# MCU.net
KiCad netlist of a schematic drawn in Altium Designer
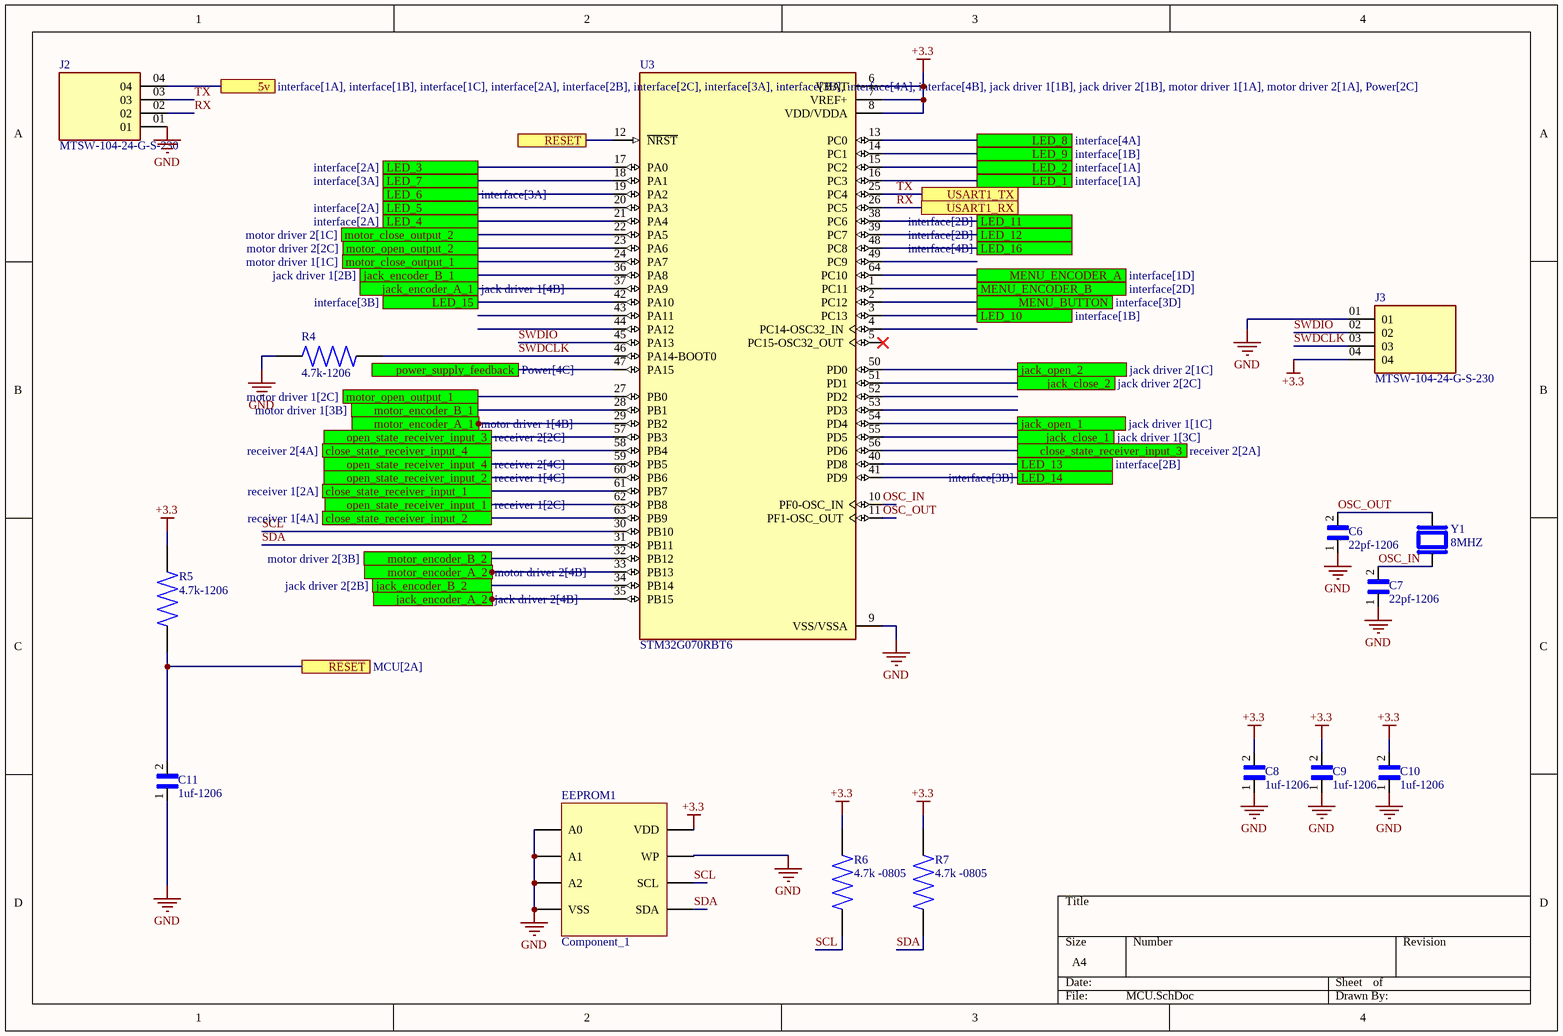
[diagram p0: MCU.SchDoc]

(export (version "E")
  (design (tool "Eeschema 10.0.6"))
  (components
    (comp (ref "C6")
      (value "22pf-1206")
      (footprint "CAPC3216X180N")
      (description "1ÂµF Â±20% 50V Ceramic Capacitor X8R 1206 (3216 Metric)")
      (fields (field (name "MF") "TDK") (field (name "MP") "CGA5L3X8R1H105M160AB"))
      (libsource (lib "cap-1206") (part "CGA5L3X8R1H105M160AB"))
    )
    (comp (ref "C7")
      (value "22pf-1206")
      (footprint "CAPC3216X180N")
      (description "1ÂµF Â±20% 50V Ceramic Capacitor X8R 1206 (3216 Metric)")
      (fields (field (name "MF") "TDK") (field (name "MP") "CGA5L3X8R1H105M160AB"))
      (libsource (lib "cap-1206") (part "CGA5L3X8R1H105M160AB"))
    )
    (comp (ref "C8")
      (value "1uf-1206")
      (footprint "CAPC3216X180N")
      (description "1ÂµF Â±20% 50V Ceramic Capacitor X8R 1206 (3216 Metric)")
      (fields (field (name "MF") "TDK") (field (name "MP") "CGA5L3X8R1H105M160AB"))
      (libsource (lib "cap-1206") (part "CGA5L3X8R1H105M160AB"))
    )
    (comp (ref "C9")
      (value "1uf-1206")
      (footprint "CAPC3216X180N")
      (description "1ÂµF Â±20% 50V Ceramic Capacitor X8R 1206 (3216 Metric)")
      (fields (field (name "MF") "TDK") (field (name "MP") "CGA5L3X8R1H105M160AB"))
      (libsource (lib "cap-1206") (part "CGA5L3X8R1H105M160AB"))
    )
    (comp (ref "C10")
      (value "1uf-1206")
      (footprint "CAPC3216X180N")
      (description "1ÂµF Â±20% 50V Ceramic Capacitor X8R 1206 (3216 Metric)")
      (fields (field (name "MF") "TDK") (field (name "MP") "CGA5L3X8R1H105M160AB"))
      (libsource (lib "cap-1206") (part "CGA5L3X8R1H105M160AB"))
    )
    (comp (ref "C11")
      (value "1uf-1206")
      (footprint "CAPC3216X180N")
      (description "1ÂµF Â±20% 50V Ceramic Capacitor X8R 1206 (3216 Metric)")
      (fields (field (name "MF") "TDK") (field (name "MP") "CGA5L3X8R1H105M160AB"))
      (libsource (lib "cap-1206") (part "CGA5L3X8R1H105M160AB"))
    )
    (comp (ref "EEPROM1")
      (value "Component_1")
      (footprint "SOIC127P602X172-8N")
      (libsource (lib "FM24CL64B") (part "Component_1"))
    )
    (comp (ref "J2")
      (value "MTSW-104-24-G-S-230")
      (footprint "SAMTEC_MTSW-104-24-G-S-230")
      (libsource (lib "4pin2.54mm") (part "MTSW-104-24-G-S-230"))
    )
    (comp (ref "J3")
      (value "MTSW-104-24-G-S-230")
      (footprint "SAMTEC_MTSW-104-24-G-S-230")
      (libsource (lib "") (part "MTSW-104-24-G-S-230_1"))
    )
    (comp (ref "R4")
      (value "4.7k-1206")
      (footprint "RESC3015X65N")
      (description "Res Thin Film 1206 10K Ohm 0.1% 1/8W Â±25ppm/Â°C Molded SMD SMD Paper T/R")
      (fields (field (name "MF") "TE Connectivity") (field (name "MP") "CPF1206B10KE1"))
      (libsource (lib "resistor-1206") (part "CPF1206B10KE1"))
    )
    (comp (ref "R5")
      (value "4.7k-1206")
      (footprint "RESC3015X65N")
      (description "Res Thin Film 1206 10K Ohm 0.1% 1/8W Â±25ppm/Â°C Molded SMD SMD Paper T/R")
      (fields (field (name "MF") "TE Connectivity") (field (name "MP") "CPF1206B10KE1"))
      (libsource (lib "resistor-1206") (part "CPF1206B10KE1"))
    )
    (comp (ref "R6")
      (value "4.7k -0805")
      (footprint "RESC2012X65N")
      (description "Fixed Resistor CRGCQ 0805 470R 5%")
      (fields (field (name "MF") "TE Connectivity") (field (name "MP") "CRGCQ0805J470R"))
      (libsource (lib "res0805") (part "CRGCQ0805J470R"))
    )
    (comp (ref "R7")
      (value "4.7k -0805")
      (footprint "RESC2012X65N")
      (description "Fixed Resistor CRGCQ 0805 470R 5%")
      (fields (field (name "MF") "TE Connectivity") (field (name "MP") "CRGCQ0805J470R"))
      (libsource (lib "res0805") (part "CRGCQ0805J470R"))
    )
    (comp (ref "U3")
      (value "STM32G070RBT6")
      (footprint "QFP50P1200X1200X160-64N")
      (fields (field (name "MF") "STMicroelectronics"))
      (libsource (lib "STM32G070RBT6") (part "STM32G070RBT6"))
    )
    (comp (ref "Y1")
      (value "8MHZ")
      (footprint "XTAL_ABLS2-12.000MHZ-D4Y-T")
      (description "HC/49US (AT49) LOW PROFILE SURFACE MOUNT MICROPROCESSOR CRYSTAL")
      (fields (field (name "MP") "ABLS2-12.000MHZ-D4Y-T") (field (name "MF") "Abracon"))
      (libsource (lib "CRYSTAL") (part "ABLS2-12.000MHZ-D4Y-T"))
    )
  )
  (nets
    (net (code "1") (name "+3.3") (class "Default")
      (node (ref "C10") (pin "2") (pinfunction "2_2") (pintype "passive"))
      (node (ref "C8") (pin "2") (pinfunction "2_2") (pintype "passive"))
      (node (ref "C9") (pin "2") (pinfunction "2_2") (pintype "passive"))
      (node (ref "EEPROM1") (pin "7") (pinfunction "VDD_7") (pintype "passive"))
      (node (ref "J3") (pin "04") (pinfunction "04_04") (pintype "passive"))
      (node (ref "R5") (pin "2") (pinfunction "2_2") (pintype "passive"))
      (node (ref "R6") (pin "2") (pinfunction "2_2") (pintype "passive"))
      (node (ref "R7") (pin "2") (pinfunction "2_2") (pintype "passive"))
      (node (ref "U3") (pin "6") (pinfunction "VBAT_6") (pintype "power_in"))
      (node (ref "U3") (pin "7") (pinfunction "VREF+_7") (pintype "power_in"))
      (node (ref "U3") (pin "8") (pinfunction "VDD/VDDA_8") (pintype "power_in"))
    )
    (net (code "2") (name "/5v") (class "Default")
      (node (ref "J2") (pin "04") (pinfunction "04_04") (pintype "passive"))
    )
    (net (code "3") (name "/LED_1") (class "Default")
      (node (ref "U3") (pin "16") (pinfunction "PC3_16") (pintype "bidirectional"))
    )
    (net (code "4") (name "/LED_2") (class "Default")
      (node (ref "U3") (pin "15") (pinfunction "PC2_15") (pintype "bidirectional"))
    )
    (net (code "5") (name "/LED_3") (class "Default")
      (node (ref "U3") (pin "17") (pinfunction "PA0_17") (pintype "bidirectional"))
    )
    (net (code "6") (name "/LED_4") (class "Default")
      (node (ref "U3") (pin "21") (pinfunction "PA4_21") (pintype "bidirectional"))
    )
    (net (code "7") (name "/LED_5") (class "Default")
      (node (ref "U3") (pin "20") (pinfunction "PA3_20") (pintype "bidirectional"))
    )
    (net (code "8") (name "/LED_6") (class "Default")
      (node (ref "U3") (pin "19") (pinfunction "PA2_19") (pintype "bidirectional"))
    )
    (net (code "9") (name "/LED_7") (class "Default")
      (node (ref "U3") (pin "18") (pinfunction "PA1_18") (pintype "bidirectional"))
    )
    (net (code "10") (name "/LED_8") (class "Default")
      (node (ref "U3") (pin "13") (pinfunction "PC0_13") (pintype "bidirectional"))
    )
    (net (code "11") (name "/LED_9") (class "Default")
      (node (ref "U3") (pin "14") (pinfunction "PC1_14") (pintype "bidirectional"))
    )
    (net (code "12") (name "/LED_10") (class "Default")
      (node (ref "U3") (pin "3") (pinfunction "PC13_3") (pintype "bidirectional"))
    )
    (net (code "13") (name "/LED_11") (class "Default")
      (node (ref "U3") (pin "38") (pinfunction "PC6_38") (pintype "bidirectional"))
    )
    (net (code "14") (name "/LED_12") (class "Default")
      (node (ref "U3") (pin "39") (pinfunction "PC7_39") (pintype "bidirectional"))
    )
    (net (code "15") (name "/LED_13") (class "Default")
      (node (ref "U3") (pin "40") (pinfunction "PD8_40") (pintype "bidirectional"))
    )
    (net (code "16") (name "/LED_14") (class "Default")
      (node (ref "U3") (pin "41") (pinfunction "PD9_41") (pintype "bidirectional"))
    )
    (net (code "17") (name "/LED_15") (class "Default")
      (node (ref "U3") (pin "42") (pinfunction "PA10_42") (pintype "bidirectional"))
    )
    (net (code "18") (name "/LED_16") (class "Default")
      (node (ref "U3") (pin "48") (pinfunction "PC8_48") (pintype "bidirectional"))
    )
    (net (code "19") (name "/MENU_BUTTON") (class "Default")
      (node (ref "U3") (pin "2") (pinfunction "PC12_2") (pintype "bidirectional"))
    )
    (net (code "20") (name "/MENU_ENCODER_A") (class "Default")
      (node (ref "U3") (pin "64") (pinfunction "PC10_64") (pintype "bidirectional"))
    )
    (net (code "21") (name "/MENU_ENCODER_B") (class "Default")
      (node (ref "U3") (pin "1") (pinfunction "PC11_1") (pintype "bidirectional"))
    )
    (net (code "22") (name "/OSC_IN") (class "Default")
      (node (ref "C7") (pin "2") (pinfunction "2_2") (pintype "passive"))
      (node (ref "U3") (pin "10") (pinfunction "PF0-OSC_IN_10") (pintype "bidirectional"))
      (node (ref "Y1") (pin "1") (pinfunction "1_1") (pintype "passive"))
    )
    (net (code "23") (name "/OSC_OUT") (class "Default")
      (node (ref "C6") (pin "2") (pinfunction "2_2") (pintype "passive"))
      (node (ref "U3") (pin "11") (pinfunction "PF1-OSC_OUT_11") (pintype "bidirectional"))
      (node (ref "Y1") (pin "2") (pinfunction "2_2") (pintype "passive"))
    )
    (net (code "24") (name "/RESET") (class "Default")
      (node (ref "C11") (pin "2") (pinfunction "2_2") (pintype "passive"))
      (node (ref "R5") (pin "1") (pinfunction "1_1") (pintype "passive"))
      (node (ref "U3") (pin "12") (pinfunction "~{NRST}_12") (pintype "input"))
    )
    (net (code "25") (name "/RX") (class "Default")
      (node (ref "J2") (pin "02") (pinfunction "02_02") (pintype "passive"))
      (node (ref "U3") (pin "26") (pinfunction "PC5_26") (pintype "bidirectional"))
    )
    (net (code "26") (name "/SCL") (class "Default")
      (node (ref "EEPROM1") (pin "5") (pinfunction "SCL_5") (pintype "passive"))
      (node (ref "R6") (pin "1") (pinfunction "1_1") (pintype "passive"))
      (node (ref "U3") (pin "30") (pinfunction "PB10_30") (pintype "bidirectional"))
    )
    (net (code "27") (name "/SDA") (class "Default")
      (node (ref "EEPROM1") (pin "4") (pinfunction "SDA_4") (pintype "passive"))
      (node (ref "R7") (pin "1") (pinfunction "1_1") (pintype "passive"))
      (node (ref "U3") (pin "31") (pinfunction "PB11_31") (pintype "bidirectional"))
    )
    (net (code "28") (name "/SWDCLK") (class "Default")
      (node (ref "J3") (pin "03") (pinfunction "03_03") (pintype "passive"))
      (node (ref "R4") (pin "1") (pinfunction "1_1") (pintype "passive"))
      (node (ref "U3") (pin "46") (pinfunction "PA14-BOOT0_46") (pintype "bidirectional"))
    )
    (net (code "29") (name "/SWDIO") (class "Default")
      (node (ref "J3") (pin "02") (pinfunction "02_02") (pintype "passive"))
      (node (ref "U3") (pin "45") (pinfunction "PA13_45") (pintype "bidirectional"))
    )
    (net (code "30") (name "/TX") (class "Default")
      (node (ref "J2") (pin "03") (pinfunction "03_03") (pintype "passive"))
      (node (ref "U3") (pin "25") (pinfunction "PC4_25") (pintype "bidirectional"))
    )
    (net (code "31") (name "/close_state_receiver_input_1") (class "Default")
      (node (ref "U3") (pin "61") (pinfunction "PB7_61") (pintype "bidirectional"))
    )
    (net (code "32") (name "/close_state_receiver_input_2") (class "Default")
      (node (ref "U3") (pin "63") (pinfunction "PB9_63") (pintype "bidirectional"))
    )
    (net (code "33") (name "/close_state_receiver_input_3") (class "Default")
      (node (ref "U3") (pin "56") (pinfunction "PD6_56") (pintype "bidirectional"))
    )
    (net (code "34") (name "/close_state_receiver_input_4") (class "Default")
      (node (ref "U3") (pin "58") (pinfunction "PB4_58") (pintype "bidirectional"))
    )
    (net (code "35") (name "/jack_close_1") (class "Default")
      (node (ref "U3") (pin "55") (pinfunction "PD5_55") (pintype "bidirectional"))
    )
    (net (code "36") (name "/jack_close_2") (class "Default")
      (node (ref "U3") (pin "51") (pinfunction "PD1_51") (pintype "bidirectional"))
    )
    (net (code "37") (name "/jack_encoder_A_1") (class "Default")
      (node (ref "U3") (pin "37") (pinfunction "PA9_37") (pintype "bidirectional"))
    )
    (net (code "38") (name "/jack_encoder_A_2") (class "Default")
      (node (ref "U3") (pin "35") (pinfunction "PB15_35") (pintype "bidirectional"))
    )
    (net (code "39") (name "/jack_encoder_B_1") (class "Default")
      (node (ref "U3") (pin "36") (pinfunction "PA8_36") (pintype "bidirectional"))
    )
    (net (code "40") (name "/jack_encoder_B_2") (class "Default")
      (node (ref "U3") (pin "34") (pinfunction "PB14_34") (pintype "bidirectional"))
    )
    (net (code "41") (name "/jack_open_1") (class "Default")
      (node (ref "U3") (pin "54") (pinfunction "PD4_54") (pintype "bidirectional"))
    )
    (net (code "42") (name "/jack_open_2") (class "Default")
      (node (ref "U3") (pin "50") (pinfunction "PD0_50") (pintype "bidirectional"))
    )
    (net (code "43") (name "/motor_close_output_1") (class "Default")
      (node (ref "U3") (pin "24") (pinfunction "PA7_24") (pintype "bidirectional"))
    )
    (net (code "44") (name "/motor_close_output_2") (class "Default")
      (node (ref "U3") (pin "22") (pinfunction "PA5_22") (pintype "bidirectional"))
    )
    (net (code "45") (name "/motor_encoder_A_1") (class "Default")
      (node (ref "U3") (pin "29") (pinfunction "PB2_29") (pintype "bidirectional"))
    )
    (net (code "46") (name "/motor_encoder_A_2") (class "Default")
      (node (ref "U3") (pin "33") (pinfunction "PB13_33") (pintype "bidirectional"))
    )
    (net (code "47") (name "/motor_encoder_B_1") (class "Default")
      (node (ref "U3") (pin "28") (pinfunction "PB1_28") (pintype "bidirectional"))
    )
    (net (code "48") (name "/motor_encoder_B_2") (class "Default")
      (node (ref "U3") (pin "32") (pinfunction "PB12_32") (pintype "bidirectional"))
    )
    (net (code "49") (name "/motor_open_output_1") (class "Default")
      (node (ref "U3") (pin "27") (pinfunction "PB0_27") (pintype "bidirectional"))
    )
    (net (code "50") (name "/motor_open_output_2") (class "Default")
      (node (ref "U3") (pin "23") (pinfunction "PA6_23") (pintype "bidirectional"))
    )
    (net (code "51") (name "/open_state_receiver_input_1") (class "Default")
      (node (ref "U3") (pin "62") (pinfunction "PB8_62") (pintype "bidirectional"))
    )
    (net (code "52") (name "/open_state_receiver_input_2") (class "Default")
      (node (ref "U3") (pin "60") (pinfunction "PB6_60") (pintype "bidirectional"))
    )
    (net (code "53") (name "/open_state_receiver_input_3") (class "Default")
      (node (ref "U3") (pin "57") (pinfunction "PB3_57") (pintype "bidirectional"))
    )
    (net (code "54") (name "/open_state_receiver_input_4") (class "Default")
      (node (ref "U3") (pin "59") (pinfunction "PB5_59") (pintype "bidirectional"))
    )
    (net (code "55") (name "/power_supply_feedback") (class "Default")
      (node (ref "U3") (pin "47") (pinfunction "PA15_47") (pintype "bidirectional"))
    )
    (net (code "56") (name "GND") (class "Default")
      (node (ref "C10") (pin "1") (pinfunction "1_1") (pintype "passive"))
      (node (ref "C11") (pin "1") (pinfunction "1_1") (pintype "passive"))
      (node (ref "C6") (pin "1") (pinfunction "1_1") (pintype "passive"))
      (node (ref "C7") (pin "1") (pinfunction "1_1") (pintype "passive"))
      (node (ref "C8") (pin "1") (pinfunction "1_1") (pintype "passive"))
      (node (ref "C9") (pin "1") (pinfunction "1_1") (pintype "passive"))
      (node (ref "EEPROM1") (pin "0") (pinfunction "A0_0") (pintype "passive"))
      (node (ref "EEPROM1") (pin "1") (pinfunction "A1_1") (pintype "passive"))
      (node (ref "EEPROM1") (pin "2") (pinfunction "A2_2") (pintype "passive"))
      (node (ref "EEPROM1") (pin "3") (pinfunction "VSS_3") (pintype "passive"))
      (node (ref "EEPROM1") (pin "6") (pinfunction "WP_6") (pintype "passive"))
      (node (ref "J2") (pin "01") (pinfunction "01_01") (pintype "passive"))
      (node (ref "J3") (pin "01") (pinfunction "01_01") (pintype "passive"))
      (node (ref "R4") (pin "2") (pinfunction "2_2") (pintype "passive"))
      (node (ref "U3") (pin "9") (pinfunction "VSS/VSSA_9") (pintype "power_in"))
    )
    (net (code "57") (name "unconnected-(U3-PA11-Pad43)") (class "Default")
      (node (ref "U3") (pin "43") (pinfunction "PA11_43") (pintype "bidirectional"))
    )
    (net (code "58") (name "unconnected-(U3-PA12-Pad44)") (class "Default")
      (node (ref "U3") (pin "44") (pinfunction "PA12_44") (pintype "bidirectional"))
    )
    (net (code "59") (name "unconnected-(U3-PC9-Pad49)") (class "Default")
      (node (ref "U3") (pin "49") (pinfunction "PC9_49") (pintype "bidirectional"))
    )
    (net (code "60") (name "unconnected-(U3-PC14-OSC32_IN-Pad4)") (class "Default")
      (node (ref "U3") (pin "4") (pinfunction "PC14-OSC32_IN_4") (pintype "bidirectional"))
    )
    (net (code "61") (name "unconnected-(U3-PC15-OSC32_OUT-Pad5)") (class "Default")
      (node (ref "U3") (pin "5") (pinfunction "PC15-OSC32_OUT_5") (pintype "bidirectional+no_connect"))
    )
    (net (code "62") (name "unconnected-(U3-PD2-Pad52)") (class "Default")
      (node (ref "U3") (pin "52") (pinfunction "PD2_52") (pintype "bidirectional"))
    )
    (net (code "63") (name "unconnected-(U3-PD3-Pad53)") (class "Default")
      (node (ref "U3") (pin "53") (pinfunction "PD3_53") (pintype "bidirectional"))
    )
  )
)
